# LLC.net
KiCad netlist of a schematic drawn in Altium Designer
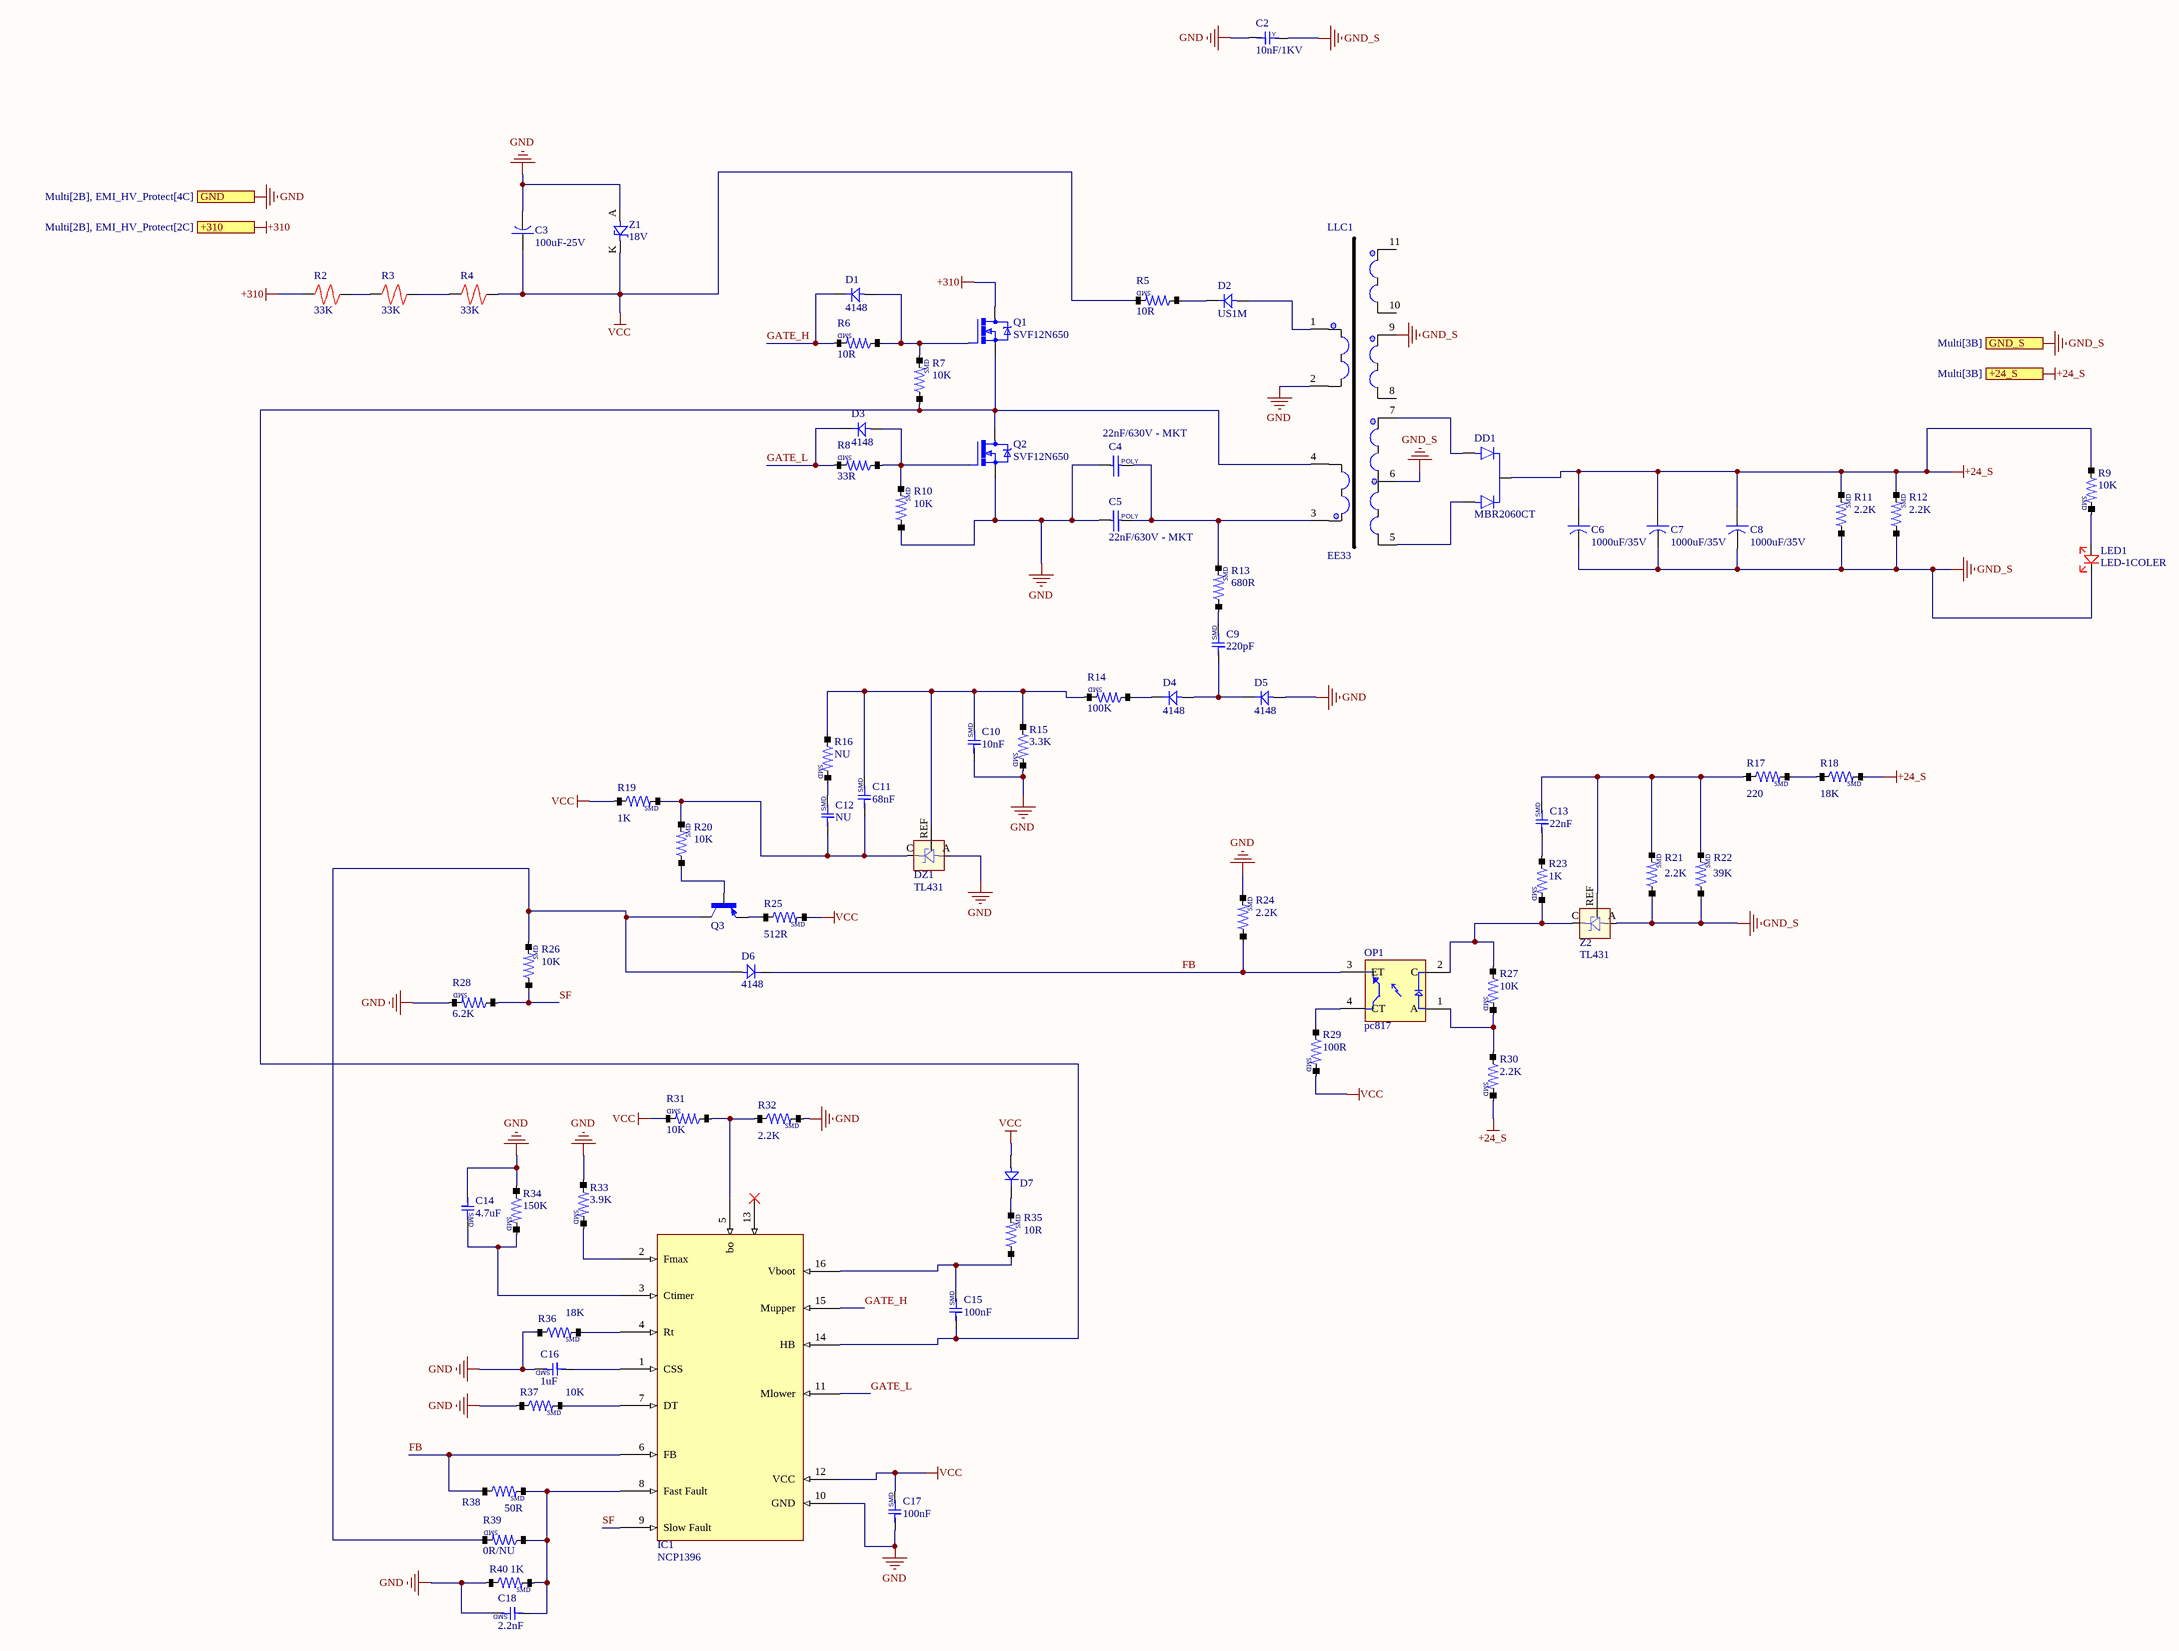
[diagram p0: LLC.SchDoc]

(export (version "E")
  (design (tool "Eeschema 10.0.6"))
  (components
    (comp (ref "C2")
      (value "10nF/1KV")
      (footprint "CAP_Y_2KV")
      (libsource (lib "kave-eng-pro") (part "CAP_Y"))
    )
    (comp (ref "C3")
      (value "100uF-25V")
      (footprint "cap/330u/16v")
      (libsource (lib "kave-eng-pro") (part "cap-electrolit"))
    )
    (comp (ref "C4")
      (value "22nF/630V - MKT")
      (footprint "CAP-POLY-0.47uF-400V")
      (libsource (lib "kave-eng-pro") (part "cap-poly"))
    )
    (comp (ref "C5")
      (value "22nF/630V - MKT")
      (footprint "CAP-POLY-0.47uF-400V")
      (libsource (lib "kave-eng-pro") (part "cap-poly"))
    )
    (comp (ref "C6")
      (value "1000uF/35V")
      (footprint "CAP-EL_P5MM")
      (libsource (lib "kave-eng-pro") (part "cap-electrolit"))
    )
    (comp (ref "C7")
      (value "1000uF/35V")
      (footprint "CAP-EL_P5MM")
      (libsource (lib "kave-eng-pro") (part "cap-electrolit"))
    )
    (comp (ref "C8")
      (value "1000uF/35V")
      (footprint "CAP-EL_P5MM")
      (libsource (lib "kave-eng-pro") (part "cap-electrolit"))
    )
    (comp (ref "C9") (value "220pF") (footprint "CAP-0805") (libsource (lib "kave-eng-pro") (part "cap_smd")))
    (comp (ref "C10") (value "10nF") (footprint "CAP-0603") (libsource (lib "kave-eng-pro") (part "cap_smd")))
    (comp (ref "C11") (value "68nF") (footprint "CAP-0603") (libsource (lib "kave-eng-pro") (part "cap_smd")))
    (comp (ref "C12") (value "NU") (footprint "CAP-0603") (libsource (lib "kave-eng-pro") (part "cap_smd")))
    (comp (ref "C13") (value "22nF") (footprint "CAP-0603") (libsource (lib "kave-eng-pro") (part "cap_smd")))
    (comp (ref "C14")
      (value "4.7uF")
      (footprint "CAP-0805")
      (libsource (lib "kave-eng-pro") (part "cap_smd"))
    )
    (comp (ref "C15")
      (value "100nF")
      (footprint "CAP-1206")
      (libsource (lib "kave-eng-pro") (part "cap_smd"))
    )
    (comp (ref "C16") (value "1uF") (footprint "CAP-0805") (libsource (lib "kave-eng-pro") (part "cap_smd")))
    (comp (ref "C17")
      (value "100nF")
      (footprint "CAP-0603")
      (libsource (lib "kave-eng-pro") (part "cap_smd"))
    )
    (comp (ref "C18")
      (value "2.2nF")
      (footprint "CAP-0603")
      (libsource (lib "kave-eng-pro") (part "cap_smd"))
    )
    (comp (ref "D1")
      (value "4148")
      (footprint "mini_melf")
      (libsource (lib "kave-eng-pro") (part "DIOD/RECTIFIERS"))
    )
    (comp (ref "D2")
      (value "US1M")
      (footprint "DIOD/1N4007/SMD")
      (libsource (lib "kave-eng-pro") (part "DIOD/RECTIFIERS"))
    )
    (comp (ref "D3")
      (value "4148")
      (footprint "mini_melf")
      (libsource (lib "kave-eng-pro") (part "DIOD/RECTIFIERS"))
    )
    (comp (ref "D4")
      (value "4148")
      (footprint "mini_melf")
      (libsource (lib "kave-eng-pro") (part "DIOD/RECTIFIERS"))
    )
    (comp (ref "D5")
      (value "4148")
      (footprint "mini_melf")
      (libsource (lib "kave-eng-pro") (part "DIOD/RECTIFIERS"))
    )
    (comp (ref "D6")
      (value "4148")
      (footprint "mini_melf")
      (libsource (lib "kave-eng-pro") (part "DIOD/RECTIFIERS"))
    )
    (comp (ref "D7")
      (value "DIOD/RECTIFIERS")
      (footprint "DIOD/1N4007/SMD")
      (libsource (lib "kave-eng-pro") (part "DIOD/RECTIFIERS"))
    )
    (comp (ref "DD1")
      (value "MBR2060CT")
      (footprint "TO220AB")
      (libsource (lib "kave-eng-pro") (part "DIOD_double"))
    )
    (comp (ref "DZ1") (value "TL431") (footprint "TL431") (libsource (lib "kave-eng-pro") (part "TL431")))
    (comp (ref "IC1")
      (value "NCP1396")
      (footprint "TL494_SMD")
      (libsource (lib "kave-eng-pro") (part "NCP1396"))
    )
    (comp (ref "LED1")
      (value "LED-1COLER")
      (footprint "led/3MM/DIP")
      (libsource (lib "kave-eng-pro") (part "LED-1COLER"))
    )
    (comp (ref "LLC1")
      (value "EE33")
      (footprint "EE33")
      (libsource (lib "kave-eng-pro") (part "TRANS_RT03_LLC"))
    )
    (comp (ref "OP1") (value "pc817") (footprint "pc817") (libsource (lib "kave-eng-pro") (part "pc817")))
    (comp (ref "Q1")
      (value "SVF12N650")
      (footprint "TO-220")
      (libsource (lib "kave-eng-pro") (part "MOSFET_N_CH"))
    )
    (comp (ref "Q2")
      (value "SVF12N650")
      (footprint "TO-220")
      (libsource (lib "kave-eng-pro") (part "MOSFET_N_CH"))
    )
    (comp (ref "Q3") (value "~") (footprint "SOT23") (libsource (lib "kave-eng-pro") (part "PNP")))
    (comp (ref "R2") (value "33K") (footprint "RES/1W") (libsource (lib "kave-eng-pro") (part "RES/{lt}1W")))
    (comp (ref "R3")
      (value "33K")
      (footprint "RES/0.25W")
      (libsource (lib "kave-eng-pro") (part "RES/{lt}1W"))
    )
    (comp (ref "R4")
      (value "33K")
      (footprint "RES/0.25W")
      (libsource (lib "kave-eng-pro") (part "RES/{lt}1W"))
    )
    (comp (ref "R5") (value "10R") (footprint "RES/1206") (libsource (lib "kave-eng-pro") (part "RES/SMD")))
    (comp (ref "R6") (value "10R") (footprint "RES/1206") (libsource (lib "kave-eng-pro") (part "RES/SMD")))
    (comp (ref "R7") (value "10K") (footprint "RES/0603") (libsource (lib "") (part "RES/SMD_2")))
    (comp (ref "R8") (value "33R") (footprint "RES/1206") (libsource (lib "kave-eng-pro") (part "RES/SMD")))
    (comp (ref "R9") (value "10K") (footprint "RES/1206") (libsource (lib "") (part "RES/SMD_3")))
    (comp (ref "R10") (value "10K") (footprint "RES/0603") (libsource (lib "") (part "RES/SMD_2")))
    (comp (ref "R11") (value "2.2K") (footprint "RES/1206") (libsource (lib "") (part "RES/SMD_2")))
    (comp (ref "R12") (value "2.2K") (footprint "RES/1206") (libsource (lib "") (part "RES/SMD_2")))
    (comp (ref "R13") (value "680R") (footprint "RES/0603") (libsource (lib "") (part "RES/SMD_2")))
    (comp (ref "R14") (value "100K") (footprint "RES/0603") (libsource (lib "kave-eng-pro") (part "RES/SMD")))
    (comp (ref "R15") (value "3.3K") (footprint "RES/0603") (libsource (lib "") (part "RES/SMD_3")))
    (comp (ref "R16") (value "NU") (footprint "RES/0603") (libsource (lib "") (part "RES/SMD_3")))
    (comp (ref "R17") (value "220") (footprint "RES/0603") (libsource (lib "") (part "RES/SMD_1")))
    (comp (ref "R18") (value "18K") (footprint "RES/0603") (libsource (lib "") (part "RES/SMD_1")))
    (comp (ref "R19") (value "1K") (footprint "RES/0603") (libsource (lib "") (part "RES/SMD_1")))
    (comp (ref "R20") (value "10K") (footprint "RES/0603") (libsource (lib "") (part "RES/SMD_2")))
    (comp (ref "R21") (value "2.2K") (footprint "RES/0603") (libsource (lib "") (part "RES/SMD_2")))
    (comp (ref "R22") (value "39K") (footprint "RES/0603") (libsource (lib "") (part "RES/SMD_2")))
    (comp (ref "R23") (value "1K") (footprint "RES/0603") (libsource (lib "") (part "RES/SMD_3")))
    (comp (ref "R24") (value "2.2K") (footprint "RES/0603") (libsource (lib "") (part "RES/SMD_2")))
    (comp (ref "R25") (value "512R") (footprint "RES/0603") (libsource (lib "") (part "RES/SMD_1")))
    (comp (ref "R26") (value "10K") (footprint "RES/0603") (libsource (lib "") (part "RES/SMD_2")))
    (comp (ref "R27") (value "10K") (footprint "RES/0603") (libsource (lib "") (part "RES/SMD_3")))
    (comp (ref "R28") (value "6.2K") (footprint "RES/0603") (libsource (lib "kave-eng-pro") (part "RES/SMD")))
    (comp (ref "R29") (value "100R") (footprint "RES/0603") (libsource (lib "") (part "RES/SMD_3")))
    (comp (ref "R30") (value "2.2K") (footprint "RES/0603") (libsource (lib "") (part "RES/SMD_3")))
    (comp (ref "R31") (value "10K") (footprint "RES/0603") (libsource (lib "kave-eng-pro") (part "RES/SMD")))
    (comp (ref "R32") (value "2.2K") (footprint "RES/0603") (libsource (lib "") (part "RES/SMD_1")))
    (comp (ref "R33") (value "3.9K") (footprint "RES/0603") (libsource (lib "") (part "RES/SMD_3")))
    (comp (ref "R34") (value "150K") (footprint "RES/0603") (libsource (lib "") (part "RES/SMD_3")))
    (comp (ref "R35") (value "10R") (footprint "RES/1206") (libsource (lib "") (part "RES/SMD_2")))
    (comp (ref "R36") (value "18K") (footprint "RES/0603") (libsource (lib "") (part "RES/SMD_1")))
    (comp (ref "R37") (value "10K") (footprint "RES/0603") (libsource (lib "") (part "RES/SMD_1")))
    (comp (ref "R38") (value "50R") (footprint "RES/0603") (libsource (lib "") (part "RES/SMD_1")))
    (comp (ref "R39")
      (value "0R/NU")
      (footprint "RES/0603")
      (libsource (lib "kave-eng-pro") (part "RES/SMD"))
    )
    (comp (ref "R40") (value "1K") (footprint "RES/0603") (libsource (lib "") (part "RES/SMD_1")))
    (comp (ref "Z1")
      (value "18V")
      (footprint "DIOD/RS1J")
      (libsource (lib "kave-eng-pro") (part "zener-0.5w"))
    )
    (comp (ref "Z2") (value "TL431") (footprint "TL431") (libsource (lib "kave-eng-pro") (part "TL431")))
  )
  (nets
    (net (code "1") (name "+24_S") (class "Default")
      (node (ref "C6") (pin "+") (pintype "passive"))
      (node (ref "C7") (pin "+") (pintype "passive"))
      (node (ref "C8") (pin "+") (pintype "passive"))
      (node (ref "DD1") (pin "2") (pinfunction "C_2") (pintype "passive"))
      (node (ref "R11") (pin "2") (pinfunction "2_2") (pintype "passive"))
      (node (ref "R12") (pin "2") (pinfunction "2_2") (pintype "passive"))
      (node (ref "R18") (pin "2") (pinfunction "2_2") (pintype "passive"))
      (node (ref "R30") (pin "2") (pinfunction "2_2") (pintype "passive"))
      (node (ref "R9") (pin "1") (pinfunction "1_1") (pintype "passive"))
    )
    (net (code "2") (name "+310") (class "Default")
      (node (ref "Q1") (pin "2") (pinfunction "D_2") (pintype "passive"))
      (node (ref "R2") (pin "2") (pintype "passive"))
    )
    (net (code "3") (name "/FB") (class "Default")
      (node (ref "D6") (pin "K") (pintype "passive"))
      (node (ref "IC1") (pin "6") (pinfunction "FB_6") (pintype "input"))
      (node (ref "OP1") (pin "3") (pinfunction "ET_3") (pintype "passive"))
      (node (ref "R24") (pin "1") (pinfunction "1_1") (pintype "passive"))
      (node (ref "R38") (pin "1") (pinfunction "1_1") (pintype "passive"))
    )
    (net (code "4") (name "/GATE_H") (class "Default")
      (node (ref "D1") (pin "K") (pintype "passive"))
      (node (ref "IC1") (pin "15") (pinfunction "Mupper_15") (pintype "input"))
      (node (ref "R6") (pin "2") (pinfunction "2_2") (pintype "passive"))
    )
    (net (code "5") (name "/GATE_L") (class "Default")
      (node (ref "D3") (pin "K") (pintype "passive"))
      (node (ref "IC1") (pin "11") (pinfunction "Mlower_11") (pintype "input"))
      (node (ref "R8") (pin "2") (pinfunction "2_2") (pintype "passive"))
    )
    (net (code "6") (name "/SF") (class "Default")
      (node (ref "IC1") (pin "9") (pinfunction "Slow_Fault_9") (pintype "input"))
      (node (ref "R26") (pin "1") (pinfunction "1_1") (pintype "passive"))
      (node (ref "R28") (pin "1") (pinfunction "1_1") (pintype "passive"))
    )
    (net (code "7") (name "GND") (class "Default")
      (node (ref "C10") (pin "1") (pintype "passive"))
      (node (ref "C14") (pin "1") (pintype "passive"))
      (node (ref "C16") (pin "2") (pintype "passive"))
      (node (ref "C17") (pin "1") (pintype "passive"))
      (node (ref "C18") (pin "2") (pintype "passive"))
      (node (ref "C2") (pin "1") (pintype "passive"))
      (node (ref "C3") (pin "-") (pintype "passive"))
      (node (ref "C4") (pin "1") (pintype "passive"))
      (node (ref "C5") (pin "1") (pintype "passive"))
      (node (ref "D5") (pin "A") (pintype "passive"))
      (node (ref "DZ1") (pin "A") (pintype "passive"))
      (node (ref "IC1") (pin "10") (pinfunction "GND_10") (pintype "input"))
      (node (ref "LLC1") (pin "2") (pinfunction "0_2") (pintype "passive"))
      (node (ref "Q2") (pin "3") (pinfunction "s_3") (pintype "passive"))
      (node (ref "R10") (pin "1") (pinfunction "1_1") (pintype "passive"))
      (node (ref "R15") (pin "2") (pinfunction "2_2") (pintype "passive"))
      (node (ref "R24") (pin "2") (pinfunction "2_2") (pintype "passive"))
      (node (ref "R28") (pin "2") (pinfunction "2_2") (pintype "passive"))
      (node (ref "R32") (pin "2") (pinfunction "2_2") (pintype "passive"))
      (node (ref "R33") (pin "1") (pinfunction "1_1") (pintype "passive"))
      (node (ref "R34") (pin "1") (pinfunction "1_1") (pintype "passive"))
      (node (ref "R36") (pin "1") (pinfunction "1_1") (pintype "passive"))
      (node (ref "R37") (pin "1") (pinfunction "1_1") (pintype "passive"))
      (node (ref "R40") (pin "1") (pinfunction "1_1") (pintype "passive"))
      (node (ref "Z1") (pin "A") (pintype "passive"))
    )
    (net (code "8") (name "GND_S") (class "Default")
      (node (ref "C2") (pin "2") (pintype "passive"))
      (node (ref "C6") (pin "-") (pintype "passive"))
      (node (ref "C7") (pin "-") (pintype "passive"))
      (node (ref "C8") (pin "-") (pintype "passive"))
      (node (ref "LED1") (pin "K") (pintype "passive"))
      (node (ref "LLC1") (pin "6") (pinfunction "0_6") (pintype "passive"))
      (node (ref "LLC1") (pin "9") (pinfunction "0_9") (pintype "passive"))
      (node (ref "R11") (pin "1") (pinfunction "1_1") (pintype "passive"))
      (node (ref "R12") (pin "1") (pinfunction "1_1") (pintype "passive"))
      (node (ref "R21") (pin "1") (pinfunction "1_1") (pintype "passive"))
      (node (ref "R22") (pin "1") (pinfunction "1_1") (pintype "passive"))
      (node (ref "Z2") (pin "A") (pintype "passive"))
    )
    (net (code "9") (name "Net-(C4-Pad2)") (class "Default")
      (node (ref "C4") (pin "2") (pintype "passive"))
      (node (ref "C5") (pin "2") (pintype "passive"))
      (node (ref "LLC1") (pin "3") (pinfunction "0_3") (pintype "passive"))
      (node (ref "R13") (pin "2") (pinfunction "2_2") (pintype "passive"))
    )
    (net (code "10") (name "Net-(C9-Pad1)") (class "Default")
      (node (ref "C9") (pin "1") (pintype "passive"))
      (node (ref "D4") (pin "A") (pintype "passive"))
      (node (ref "D5") (pin "K") (pintype "passive"))
    )
    (net (code "11") (name "Net-(C9-Pad2)") (class "Default")
      (node (ref "C9") (pin "2") (pintype "passive"))
      (node (ref "R13") (pin "1") (pinfunction "1_1") (pintype "passive"))
    )
    (net (code "12") (name "Net-(C10-Pad2)") (class "Default")
      (node (ref "C10") (pin "2") (pintype "passive"))
      (node (ref "C11") (pin "2") (pintype "passive"))
      (node (ref "DZ1") (pin "REF") (pintype "passive"))
      (node (ref "R14") (pin "2") (pinfunction "2_2") (pintype "passive"))
      (node (ref "R15") (pin "1") (pinfunction "1_1") (pintype "passive"))
      (node (ref "R16") (pin "1") (pinfunction "1_1") (pintype "passive"))
    )
    (net (code "13") (name "Net-(C11-Pad1)") (class "Default")
      (node (ref "C11") (pin "1") (pintype "passive"))
      (node (ref "C12") (pin "1") (pintype "passive"))
      (node (ref "DZ1") (pin "C") (pintype "passive"))
      (node (ref "R19") (pin "2") (pinfunction "2_2") (pintype "passive"))
      (node (ref "R20") (pin "2") (pinfunction "2_2") (pintype "passive"))
    )
    (net (code "14") (name "Net-(C12-Pad2)") (class "Default")
      (node (ref "C12") (pin "2") (pintype "passive"))
      (node (ref "R16") (pin "2") (pinfunction "2_2") (pintype "passive"))
    )
    (net (code "15") (name "Net-(C13-Pad1)") (class "Default")
      (node (ref "C13") (pin "1") (pintype "passive"))
      (node (ref "R23") (pin "1") (pinfunction "1_1") (pintype "passive"))
    )
    (net (code "16") (name "Net-(C13-Pad2)") (class "Default")
      (node (ref "C13") (pin "2") (pintype "passive"))
      (node (ref "R17") (pin "1") (pinfunction "1_1") (pintype "passive"))
      (node (ref "R21") (pin "2") (pinfunction "2_2") (pintype "passive"))
      (node (ref "R22") (pin "2") (pinfunction "2_2") (pintype "passive"))
      (node (ref "Z2") (pin "REF") (pintype "passive"))
    )
    (net (code "17") (name "Net-(D2-PadA)") (class "Default")
      (node (ref "D2") (pin "A") (pintype "passive"))
      (node (ref "LLC1") (pin "1") (pinfunction "0_1") (pintype "passive"))
    )
    (net (code "18") (name "Net-(D2-PadK)") (class "Default")
      (node (ref "D2") (pin "K") (pintype "passive"))
      (node (ref "R5") (pin "1") (pinfunction "1_1") (pintype "passive"))
    )
    (net (code "19") (name "Net-(D4-PadK)") (class "Default")
      (node (ref "D4") (pin "K") (pintype "passive"))
      (node (ref "R14") (pin "1") (pinfunction "1_1") (pintype "passive"))
    )
    (net (code "20") (name "Net-(D7-PadK)") (class "Default")
      (node (ref "D7") (pin "K") (pintype "passive"))
      (node (ref "R35") (pin "2") (pinfunction "2_2") (pintype "passive"))
    )
    (net (code "21") (name "Net-(DD1-A1)") (class "Default")
      (node (ref "DD1") (pin "1") (pinfunction "A1_1") (pintype "passive"))
      (node (ref "LLC1") (pin "7") (pinfunction "0_7") (pintype "passive"))
    )
    (net (code "22") (name "Net-(DD1-A2)") (class "Default")
      (node (ref "DD1") (pin "3") (pinfunction "A2_3") (pintype "passive"))
      (node (ref "LLC1") (pin "5") (pinfunction "0_5") (pintype "passive"))
    )
    (net (code "23") (name "Net-(IC1-CSS)") (class "Default")
      (node (ref "C16") (pin "1") (pintype "passive"))
      (node (ref "IC1") (pin "1") (pinfunction "CSS_1") (pintype "input"))
    )
    (net (code "24") (name "Net-(IC1-Ctimer)") (class "Default")
      (node (ref "C14") (pin "2") (pintype "passive"))
      (node (ref "IC1") (pin "3") (pinfunction "Ctimer_3") (pintype "input"))
      (node (ref "R34") (pin "2") (pinfunction "2_2") (pintype "passive"))
    )
    (net (code "25") (name "Net-(IC1-DT)") (class "Default")
      (node (ref "IC1") (pin "7") (pinfunction "DT_7") (pintype "input"))
      (node (ref "R37") (pin "2") (pinfunction "2_2") (pintype "passive"))
    )
    (net (code "26") (name "Net-(IC1-Fast_Fault)") (class "Default")
      (node (ref "C18") (pin "1") (pintype "passive"))
      (node (ref "IC1") (pin "8") (pinfunction "Fast_Fault_8") (pintype "input"))
      (node (ref "R38") (pin "2") (pinfunction "2_2") (pintype "passive"))
      (node (ref "R39") (pin "1") (pinfunction "1_1") (pintype "passive"))
      (node (ref "R40") (pin "2") (pinfunction "2_2") (pintype "passive"))
    )
    (net (code "27") (name "Net-(IC1-Fmax)") (class "Default")
      (node (ref "IC1") (pin "2") (pinfunction "Fmax_2") (pintype "input"))
      (node (ref "R33") (pin "2") (pinfunction "2_2") (pintype "passive"))
    )
    (net (code "28") (name "Net-(IC1-HB)") (class "Default")
      (node (ref "C15") (pin "1") (pintype "passive"))
      (node (ref "IC1") (pin "14") (pinfunction "HB_14") (pintype "input"))
      (node (ref "LLC1") (pin "4") (pinfunction "0_4") (pintype "passive"))
      (node (ref "Q1") (pin "3") (pinfunction "s_3") (pintype "passive"))
      (node (ref "Q2") (pin "2") (pinfunction "D_2") (pintype "passive"))
      (node (ref "R7") (pin "1") (pinfunction "1_1") (pintype "passive"))
    )
    (net (code "29") (name "Net-(IC1-Rt)") (class "Default")
      (node (ref "IC1") (pin "4") (pinfunction "Rt_4") (pintype "input"))
      (node (ref "R36") (pin "2") (pinfunction "2_2") (pintype "passive"))
    )
    (net (code "30") (name "Net-(IC1-Vboot)") (class "Default")
      (node (ref "C15") (pin "2") (pintype "passive"))
      (node (ref "IC1") (pin "16") (pinfunction "Vboot_16") (pintype "input"))
      (node (ref "R35") (pin "1") (pinfunction "1_1") (pintype "passive"))
    )
    (net (code "31") (name "Net-(IC1-bo)") (class "Default")
      (node (ref "IC1") (pin "5") (pinfunction "bo_5") (pintype "input"))
      (node (ref "R31") (pin "1") (pinfunction "1_1") (pintype "passive"))
      (node (ref "R32") (pin "1") (pinfunction "1_1") (pintype "passive"))
    )
    (net (code "32") (name "Net-(LED1-PadA)") (class "Default")
      (node (ref "LED1") (pin "A") (pintype "passive"))
      (node (ref "R9") (pin "2") (pinfunction "2_2") (pintype "passive"))
    )
    (net (code "33") (name "Net-(OP1-A)") (class "Default")
      (node (ref "OP1") (pin "1") (pinfunction "A_1") (pintype "passive"))
      (node (ref "R27") (pin "2") (pinfunction "2_2") (pintype "passive"))
      (node (ref "R30") (pin "1") (pinfunction "1_1") (pintype "passive"))
    )
    (net (code "34") (name "Net-(OP1-C)") (class "Default")
      (node (ref "OP1") (pin "2") (pinfunction "C_2") (pintype "passive"))
      (node (ref "R23") (pin "2") (pinfunction "2_2") (pintype "passive"))
      (node (ref "R27") (pin "1") (pinfunction "1_1") (pintype "passive"))
      (node (ref "Z2") (pin "C") (pintype "passive"))
    )
    (net (code "35") (name "Net-(OP1-CT)") (class "Default")
      (node (ref "OP1") (pin "4") (pinfunction "CT_4") (pintype "passive"))
      (node (ref "R29") (pin "1") (pinfunction "1_1") (pintype "passive"))
    )
    (net (code "36") (name "Net-(Q1-G)") (class "Default")
      (node (ref "D1") (pin "A") (pintype "passive"))
      (node (ref "Q1") (pin "1") (pinfunction "G_1") (pintype "passive"))
      (node (ref "R6") (pin "1") (pinfunction "1_1") (pintype "passive"))
      (node (ref "R7") (pin "2") (pinfunction "2_2") (pintype "passive"))
    )
    (net (code "37") (name "Net-(Q2-G)") (class "Default")
      (node (ref "D3") (pin "A") (pintype "passive"))
      (node (ref "Q2") (pin "1") (pinfunction "G_1") (pintype "passive"))
      (node (ref "R10") (pin "2") (pinfunction "2_2") (pintype "passive"))
      (node (ref "R8") (pin "1") (pinfunction "1_1") (pintype "passive"))
    )
    (net (code "38") (name "Net-(Q3-B)") (class "Default")
      (node (ref "Q3") (pin "1") (pinfunction "B_1") (pintype "passive"))
      (node (ref "R20") (pin "1") (pinfunction "1_1") (pintype "passive"))
    )
    (net (code "39") (name "Net-(Q3-C)") (class "Default")
      (node (ref "D6") (pin "A") (pintype "passive"))
      (node (ref "Q3") (pin "2") (pinfunction "C_2") (pintype "passive"))
      (node (ref "R26") (pin "2") (pinfunction "2_2") (pintype "passive"))
      (node (ref "R39") (pin "2") (pinfunction "2_2") (pintype "passive"))
    )
    (net (code "40") (name "Net-(Q3-E)") (class "Default")
      (node (ref "Q3") (pin "3") (pinfunction "E_3") (pintype "passive"))
      (node (ref "R25") (pin "1") (pinfunction "1_1") (pintype "passive"))
    )
    (net (code "41") (name "Net-(R2-Pad1)") (class "Default")
      (node (ref "R2") (pin "1") (pintype "passive"))
      (node (ref "R3") (pin "2") (pintype "passive"))
    )
    (net (code "42") (name "Net-(R3-Pad1)") (class "Default")
      (node (ref "R3") (pin "1") (pintype "passive"))
      (node (ref "R4") (pin "2") (pintype "passive"))
    )
    (net (code "43") (name "Net-(R17-Pad2)") (class "Default")
      (node (ref "R17") (pin "2") (pinfunction "2_2") (pintype "passive"))
      (node (ref "R18") (pin "1") (pinfunction "1_1") (pintype "passive"))
    )
    (net (code "44") (name "VCC") (class "Default")
      (node (ref "C17") (pin "2") (pintype "passive"))
      (node (ref "C3") (pin "+") (pintype "passive"))
      (node (ref "D7") (pin "A") (pintype "passive"))
      (node (ref "IC1") (pin "12") (pinfunction "VCC_12") (pintype "input"))
      (node (ref "R19") (pin "1") (pinfunction "1_1") (pintype "passive"))
      (node (ref "R25") (pin "2") (pinfunction "2_2") (pintype "passive"))
      (node (ref "R29") (pin "2") (pinfunction "2_2") (pintype "passive"))
      (node (ref "R31") (pin "2") (pinfunction "2_2") (pintype "passive"))
      (node (ref "R4") (pin "1") (pintype "passive"))
      (node (ref "R5") (pin "2") (pinfunction "2_2") (pintype "passive"))
      (node (ref "Z1") (pin "K") (pintype "passive"))
    )
    (net (code "45") (name "unconnected-(IC1-Pad13)") (class "Default")
      (node (ref "IC1") (pin "13") (pintype "input+no_connect"))
    )
    (net (code "46") (name "unconnected-(LLC1-0-Pad8)") (class "Default")
      (node (ref "LLC1") (pin "8") (pinfunction "0_8") (pintype "passive"))
    )
    (net (code "47") (name "unconnected-(LLC1-0-Pad10)") (class "Default")
      (node (ref "LLC1") (pin "10") (pinfunction "0_10") (pintype "passive"))
    )
    (net (code "48") (name "unconnected-(LLC1-0-Pad11)") (class "Default")
      (node (ref "LLC1") (pin "11") (pinfunction "0_11") (pintype "passive"))
    )
  )
)
